# SensorSheet.net
KiCad netlist of a schematic drawn in Altium Designer
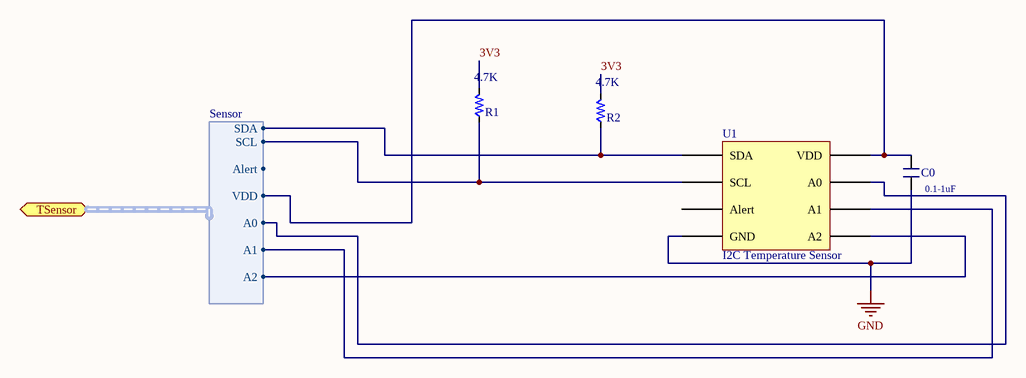
[diagram p0: SensorSheet.SchDoc]

(export (version "E")
  (design (tool "Eeschema 10.0.6"))
  (components
    (comp (ref "C0")
      (value "SCH_GENERIC_CAPACITOR_0603")
      (footprint "PCB_GENERIC_SMD_0603")
      (description "Generic SMD capacitor 0603")
      (fields (field (name "TOLERANCE") "*%") (field (name "CAPACITANCE") "0.1-1uF"))
      (libsource (lib "Generic 0603 Capacitor") (part "SCH_GENERIC_CAPACITOR_0603"))
    )
    (comp (ref "R1")
      (value "SCH_GENERIC_RESISTOR_0603")
      (footprint "PCB_GENERIC_SMD_0603")
      (description "Generic SMD resistor 0603")
      (fields (field (name "RESISTANCE") "4.7K"))
      (libsource (lib "Generic 0603 Resistor") (part "SCH_GENERIC_RESISTOR_0603"))
    )
    (comp (ref "R2")
      (value "SCH_GENERIC_RESISTOR_0603")
      (footprint "PCB_GENERIC_SMD_0603")
      (description "Generic SMD resistor 0603")
      (fields (field (name "RESISTANCE") "4.7K"))
      (libsource (lib "Generic 0603 Resistor") (part "SCH_GENERIC_RESISTOR_0603"))
    )
    (comp (ref "U1")
      (value "I2C Temperature Sensor")
      (footprint "Microchip I2C Temperature Sensor:SENSOR TEMP I2C/SMBUS 8MSOP")
      (libsource (lib "Microchip I2C Temperature Sensor") (part "Temperature Sensor Digital, Local -40°C ~ 125°C 10 b 8-MSOP, Digikey; MCP9808T-E/MSCT-ND Mfg; MCP9808T-E/MS"))
    )
  )
  (nets
    (net (code "2") (name "/3V3") (class "Default")
      (node (ref "R1") (pin "2") (pinfunction "2_2") (pintype "passive"))
      (node (ref "R2") (pin "2") (pinfunction "2_2") (pintype "passive"))
    )
    (net (code "3") (name "/A0") (class "Default")
      (node (ref "U1") (pin "7") (pinfunction "A0_7") (pintype "passive"))
    )
    (net (code "4") (name "/A1") (class "Default")
      (node (ref "U1") (pin "6") (pinfunction "A1_6") (pintype "passive"))
    )
    (net (code "5") (name "/A2") (class "Default")
      (node (ref "U1") (pin "5") (pinfunction "A2_5") (pintype "passive"))
    )
    (net (code "6") (name "/SCL") (class "Default")
      (node (ref "R1") (pin "1") (pinfunction "1_1") (pintype "passive"))
      (node (ref "U1") (pin "2") (pinfunction "SCL_2") (pintype "passive"))
    )
    (net (code "7") (name "/SDA") (class "Default")
      (node (ref "R2") (pin "1") (pinfunction "1_1") (pintype "passive"))
      (node (ref "U1") (pin "1") (pinfunction "SDA_1") (pintype "passive"))
    )
    (net (code "8") (name "/VDD") (class "Default")
      (node (ref "C0") (pin "2") (pinfunction "2_2") (pintype "passive"))
      (node (ref "U1") (pin "8") (pinfunction "VDD_8") (pintype "passive"))
    )
    (net (code "10") (name "GND") (class "Default")
      (node (ref "C0") (pin "1") (pinfunction "1_1") (pintype "passive"))
      (node (ref "U1") (pin "4") (pinfunction "GND_4") (pintype "passive"))
    )
    (net (code "11") (name "unconnected-(U1-Alert-Pad3)") (class "Default")
      (node (ref "U1") (pin "3") (pinfunction "Alert_3") (pintype "passive"))
    )
  )
)
